# RPS_ARMOR_light_PCB_2022_V1_0.net
KiCad netlist of a schematic drawn in Altium Designer
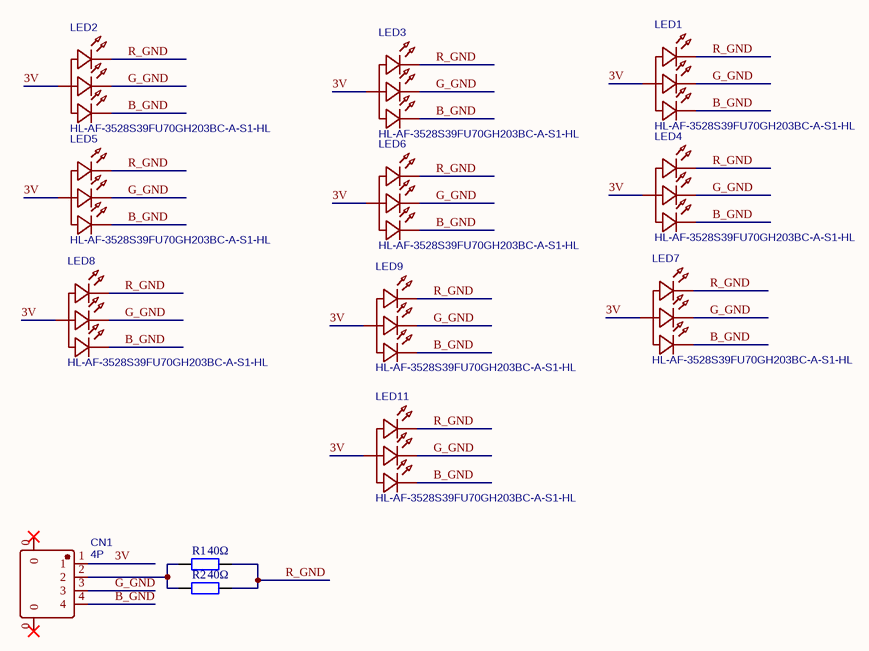
[diagram p0: RPS_ARMOR_light_PCB_2022_V1.0.SchDoc]

(export (version "E")
  (design (tool "Eeschema 10.0.6"))
  (components
    (comp (ref "CN1")
      (value "4P")
      (footprint "GH1.25-WS-4P")
      (fields
        (field (name "BOM_SUPPLIER PART") "C225127")
        (field (name "BOM_MANUFACTURER PART") "A1257WR-S-4P")
        (field (name "CONTRIBUTOR") "LCSC")
      )
      (libsource (lib "接口端子") (part "4P"))
    )
    (comp (ref "LED1")
      (value "HL-AF-3528S39FU70GH203BC-A-S1-HL")
      (footprint "LED-SMD_4P-L3.2-W2.8-P1.70-TL")
      (fields (field (name "BOM_SUPPLIER PART") "C516144") (field (name "CONTRIBUTOR") "LCSC"))
      (libsource (lib "RGB") (part "HL-AF-3528S39FU70GH203BC-A-S1-HL"))
    )
    (comp (ref "LED2")
      (value "HL-AF-3528S39FU70GH203BC-A-S1-HL")
      (footprint "LED-SMD_4P-L3.2-W2.8-P1.70-TL")
      (fields (field (name "BOM_SUPPLIER PART") "C516144") (field (name "CONTRIBUTOR") "LCSC"))
      (libsource (lib "RGB") (part "HL-AF-3528S39FU70GH203BC-A-S1-HL"))
    )
    (comp (ref "LED3")
      (value "HL-AF-3528S39FU70GH203BC-A-S1-HL")
      (footprint "LED-SMD_4P-L3.2-W2.8-P1.70-TL")
      (fields (field (name "BOM_SUPPLIER PART") "C516144") (field (name "CONTRIBUTOR") "LCSC"))
      (libsource (lib "RGB") (part "HL-AF-3528S39FU70GH203BC-A-S1-HL"))
    )
    (comp (ref "LED4")
      (value "HL-AF-3528S39FU70GH203BC-A-S1-HL")
      (footprint "LED-SMD_4P-L3.2-W2.8-P1.70-TL")
      (fields (field (name "BOM_SUPPLIER PART") "C516144") (field (name "CONTRIBUTOR") "LCSC"))
      (libsource (lib "RGB") (part "HL-AF-3528S39FU70GH203BC-A-S1-HL"))
    )
    (comp (ref "LED5")
      (value "HL-AF-3528S39FU70GH203BC-A-S1-HL")
      (footprint "LED-SMD_4P-L3.2-W2.8-P1.70-TL")
      (fields (field (name "BOM_SUPPLIER PART") "C516144") (field (name "CONTRIBUTOR") "LCSC"))
      (libsource (lib "RGB") (part "HL-AF-3528S39FU70GH203BC-A-S1-HL"))
    )
    (comp (ref "LED6")
      (value "HL-AF-3528S39FU70GH203BC-A-S1-HL")
      (footprint "LED-SMD_4P-L3.2-W2.8-P1.70-TL")
      (fields (field (name "BOM_SUPPLIER PART") "C516144") (field (name "CONTRIBUTOR") "LCSC"))
      (libsource (lib "RGB") (part "HL-AF-3528S39FU70GH203BC-A-S1-HL"))
    )
    (comp (ref "LED7")
      (value "HL-AF-3528S39FU70GH203BC-A-S1-HL")
      (footprint "LED-SMD_4P-L3.2-W2.8-P1.70-TL")
      (fields (field (name "BOM_SUPPLIER PART") "C516144") (field (name "CONTRIBUTOR") "LCSC"))
      (libsource (lib "RGB") (part "HL-AF-3528S39FU70GH203BC-A-S1-HL"))
    )
    (comp (ref "LED8")
      (value "HL-AF-3528S39FU70GH203BC-A-S1-HL")
      (footprint "LED-SMD_4P-L3.2-W2.8-P1.70-TL")
      (fields (field (name "BOM_SUPPLIER PART") "C516144") (field (name "CONTRIBUTOR") "LCSC"))
      (libsource (lib "RGB") (part "HL-AF-3528S39FU70GH203BC-A-S1-HL"))
    )
    (comp (ref "LED9")
      (value "HL-AF-3528S39FU70GH203BC-A-S1-HL")
      (footprint "LED-SMD_4P-L3.2-W2.8-P1.70-TL")
      (fields (field (name "BOM_SUPPLIER PART") "C516144") (field (name "CONTRIBUTOR") "LCSC"))
      (libsource (lib "RGB") (part "HL-AF-3528S39FU70GH203BC-A-S1-HL"))
    )
    (comp (ref "LED11")
      (value "HL-AF-3528S39FU70GH203BC-A-S1-HL")
      (footprint "LED-SMD_4P-L3.2-W2.8-P1.70-TL")
      (fields (field (name "BOM_SUPPLIER PART") "C516144") (field (name "CONTRIBUTOR") "LCSC"))
      (libsource (lib "RGB") (part "HL-AF-3528S39FU70GH203BC-A-S1-HL"))
    )
    (comp (ref "R1")
      (value "40Ω")
      (footprint "LC-0805_R")
      (description "贴片电阻")
      (libsource (lib "Miscellaneous Devices LC") (part "0603 100KΩ (1003) 1%"))
    )
    (comp (ref "R2")
      (value "40Ω")
      (footprint "LC-0805_R")
      (description "贴片电阻")
      (libsource (lib "Miscellaneous Devices LC") (part "0603 100KΩ (1003) 1%"))
    )
  )
  (nets
    (net (code "1") (name "/3V") (class "Default")
      (node (ref "CN1") (pin "1") (pinfunction "1_1") (pintype "passive"))
      (node (ref "LED1") (pin "2") (pinfunction "A_2") (pintype "passive"))
      (node (ref "LED11") (pin "2") (pinfunction "A_2") (pintype "passive"))
      (node (ref "LED2") (pin "2") (pinfunction "A_2") (pintype "passive"))
      (node (ref "LED3") (pin "2") (pinfunction "A_2") (pintype "passive"))
      (node (ref "LED4") (pin "2") (pinfunction "A_2") (pintype "passive"))
      (node (ref "LED5") (pin "2") (pinfunction "A_2") (pintype "passive"))
      (node (ref "LED6") (pin "2") (pinfunction "A_2") (pintype "passive"))
      (node (ref "LED7") (pin "2") (pinfunction "A_2") (pintype "passive"))
      (node (ref "LED8") (pin "2") (pinfunction "A_2") (pintype "passive"))
      (node (ref "LED9") (pin "2") (pinfunction "A_2") (pintype "passive"))
    )
    (net (code "2") (name "/B_GND") (class "Default")
      (node (ref "CN1") (pin "4") (pinfunction "4_4") (pintype "passive"))
      (node (ref "LED1") (pin "4") (pinfunction "B_4") (pintype "passive"))
      (node (ref "LED11") (pin "4") (pinfunction "B_4") (pintype "passive"))
      (node (ref "LED2") (pin "4") (pinfunction "B_4") (pintype "passive"))
      (node (ref "LED3") (pin "4") (pinfunction "B_4") (pintype "passive"))
      (node (ref "LED4") (pin "4") (pinfunction "B_4") (pintype "passive"))
      (node (ref "LED5") (pin "4") (pinfunction "B_4") (pintype "passive"))
      (node (ref "LED6") (pin "4") (pinfunction "B_4") (pintype "passive"))
      (node (ref "LED7") (pin "4") (pinfunction "B_4") (pintype "passive"))
      (node (ref "LED8") (pin "4") (pinfunction "B_4") (pintype "passive"))
      (node (ref "LED9") (pin "4") (pinfunction "B_4") (pintype "passive"))
    )
    (net (code "3") (name "/G_GND") (class "Default")
      (node (ref "CN1") (pin "3") (pinfunction "3_3") (pintype "passive"))
      (node (ref "LED1") (pin "3") (pinfunction "G_3") (pintype "passive"))
      (node (ref "LED11") (pin "3") (pinfunction "G_3") (pintype "passive"))
      (node (ref "LED2") (pin "3") (pinfunction "G_3") (pintype "passive"))
      (node (ref "LED3") (pin "3") (pinfunction "G_3") (pintype "passive"))
      (node (ref "LED4") (pin "3") (pinfunction "G_3") (pintype "passive"))
      (node (ref "LED5") (pin "3") (pinfunction "G_3") (pintype "passive"))
      (node (ref "LED6") (pin "3") (pinfunction "G_3") (pintype "passive"))
      (node (ref "LED7") (pin "3") (pinfunction "G_3") (pintype "passive"))
      (node (ref "LED8") (pin "3") (pinfunction "G_3") (pintype "passive"))
      (node (ref "LED9") (pin "3") (pinfunction "G_3") (pintype "passive"))
    )
    (net (code "4") (name "/R_GND") (class "Default")
      (node (ref "LED1") (pin "1") (pinfunction "R_1") (pintype "passive"))
      (node (ref "LED11") (pin "1") (pinfunction "R_1") (pintype "passive"))
      (node (ref "LED2") (pin "1") (pinfunction "R_1") (pintype "passive"))
      (node (ref "LED3") (pin "1") (pinfunction "R_1") (pintype "passive"))
      (node (ref "LED4") (pin "1") (pinfunction "R_1") (pintype "passive"))
      (node (ref "LED5") (pin "1") (pinfunction "R_1") (pintype "passive"))
      (node (ref "LED6") (pin "1") (pinfunction "R_1") (pintype "passive"))
      (node (ref "LED7") (pin "1") (pinfunction "R_1") (pintype "passive"))
      (node (ref "LED8") (pin "1") (pinfunction "R_1") (pintype "passive"))
      (node (ref "LED9") (pin "1") (pinfunction "R_1") (pintype "passive"))
      (node (ref "R1") (pin "2") (pinfunction "2_2") (pintype "passive"))
      (node (ref "R2") (pin "2") (pinfunction "2_2") (pintype "passive"))
    )
    (net (code "5") (name "Net-(CN1-Pad2)") (class "Default")
      (node (ref "CN1") (pin "2") (pinfunction "2_2") (pintype "passive"))
      (node (ref "R1") (pin "1") (pinfunction "1_1") (pintype "passive"))
      (node (ref "R2") (pin "1") (pinfunction "1_1") (pintype "passive"))
    )
    (net (code "6") (name "unconnected-(CN1-Pad0)") (class "Default")
      (node (ref "CN1") (pin "0") (pinfunction "0_0") (pintype "passive+no_connect"))
    )
    (net (code "7") (name "unconnected-(CN1-Pad0)_1") (class "Default")
      (node (ref "CN1") (pin "0") (pinfunction "0_0") (pintype "passive+no_connect"))
    )
  )
)
